# 13A-777.net
KiCad netlist of a schematic drawn in EAGLE
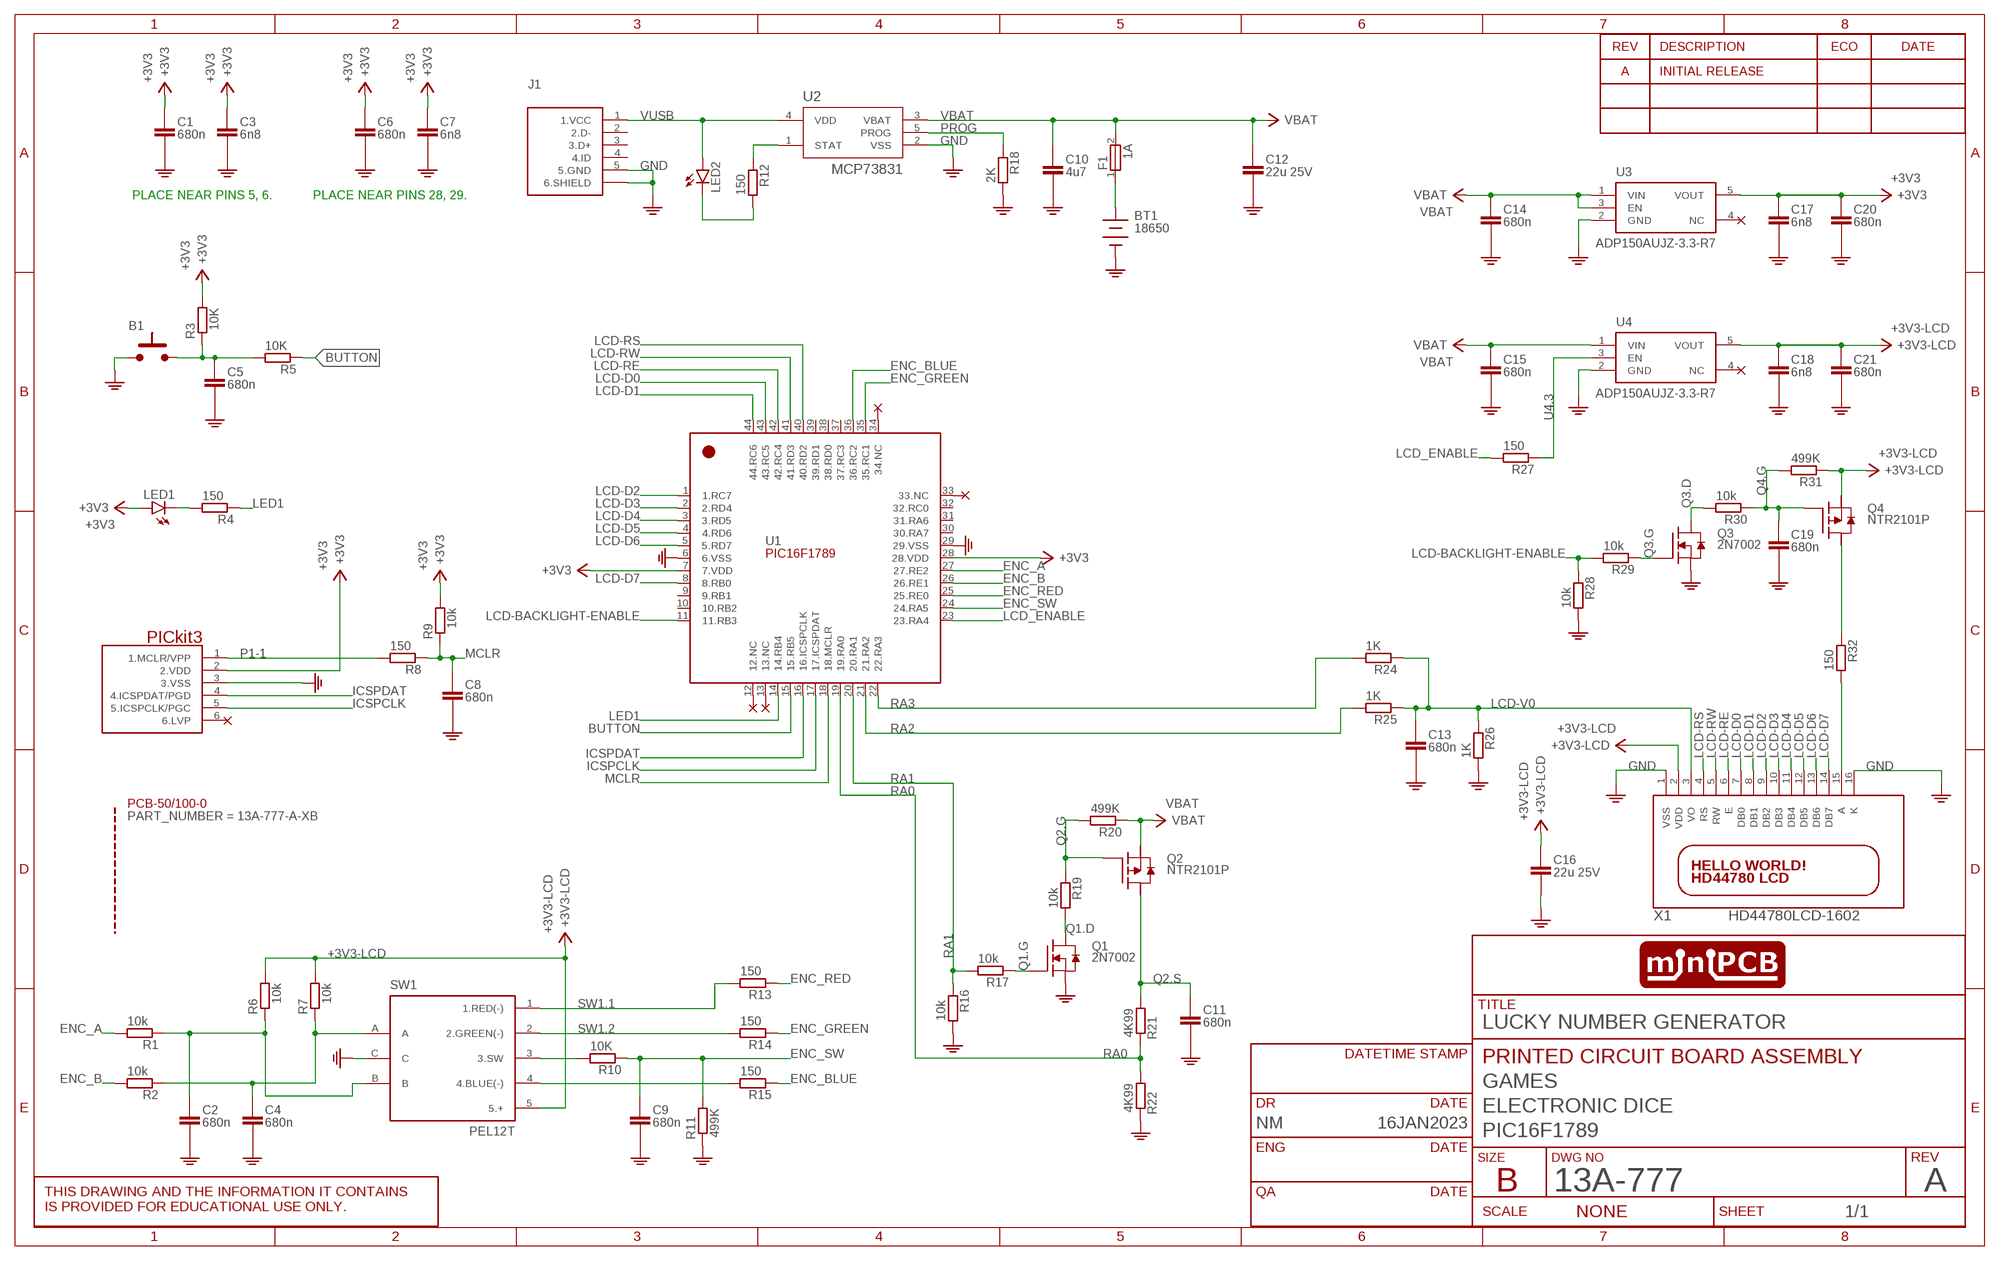
[diagram p0: schematic, sheet 1]

(export (version "E")
  (design (tool "Eeschema 10.0.6"))
  (components
    (comp (ref "B1")
      (value "PUSHBUTTON6X6MM")
      (footprint "eagle-import:6X6MM")
      (libsource (lib "eagle-import") (part "PUSHBUTTON6X6MM"))
    )
    (comp (ref "BT1")
      (value "18650")
      (footprint "eagle-import:BATTERY-18650-1-NOHOLES")
      (libsource (lib "eagle-import") (part "BATTERY18650-NOHOLES"))
    )
    (comp (ref "C1")
      (value "680n")
      (footprint "eagle-import:C1206")
      (libsource (lib "eagle-import") (part "CAPACITOR1206"))
    )
    (comp (ref "C2")
      (value "680n")
      (footprint "eagle-import:C1206")
      (libsource (lib "eagle-import") (part "CAPACITOR1206"))
    )
    (comp (ref "C3")
      (value "6n8")
      (footprint "eagle-import:C1206")
      (libsource (lib "eagle-import") (part "CAPACITOR1206"))
    )
    (comp (ref "C4")
      (value "680n")
      (footprint "eagle-import:C1206")
      (libsource (lib "eagle-import") (part "CAPACITOR1206"))
    )
    (comp (ref "C5")
      (value "680n")
      (footprint "eagle-import:C1206")
      (libsource (lib "eagle-import") (part "CAPACITOR1206"))
    )
    (comp (ref "C6")
      (value "680n")
      (footprint "eagle-import:C1206")
      (libsource (lib "eagle-import") (part "CAPACITOR1206"))
    )
    (comp (ref "C7")
      (value "6n8")
      (footprint "eagle-import:C1206")
      (libsource (lib "eagle-import") (part "CAPACITOR1206"))
    )
    (comp (ref "C8")
      (value "680n")
      (footprint "eagle-import:C1206")
      (libsource (lib "eagle-import") (part "CAPACITOR1206"))
    )
    (comp (ref "C9")
      (value "680n")
      (footprint "eagle-import:C1206")
      (libsource (lib "eagle-import") (part "CAPACITOR1206"))
    )
    (comp (ref "C10")
      (value "4u7")
      (footprint "eagle-import:C1206")
      (libsource (lib "eagle-import") (part "CAPACITOR1206"))
    )
    (comp (ref "C11")
      (value "680n")
      (footprint "eagle-import:C1206")
      (libsource (lib "eagle-import") (part "CAPACITOR1206"))
    )
    (comp (ref "C12")
      (value "22u 25V")
      (footprint "eagle-import:C3-5MM")
      (libsource (lib "eagle-import") (part "CAPACITOR3.5MM"))
    )
    (comp (ref "C13")
      (value "680n")
      (footprint "eagle-import:C1206")
      (libsource (lib "eagle-import") (part "CAPACITOR1206"))
    )
    (comp (ref "C14")
      (value "680n")
      (footprint "eagle-import:C1206")
      (libsource (lib "eagle-import") (part "CAPACITOR1206"))
    )
    (comp (ref "C15")
      (value "680n")
      (footprint "eagle-import:C1206")
      (libsource (lib "eagle-import") (part "CAPACITOR1206"))
    )
    (comp (ref "C16")
      (value "22u 25V")
      (footprint "eagle-import:C3-5MM")
      (libsource (lib "eagle-import") (part "CAPACITOR3.5MM"))
    )
    (comp (ref "C17")
      (value "6n8")
      (footprint "eagle-import:C1206")
      (libsource (lib "eagle-import") (part "CAPACITOR1206"))
    )
    (comp (ref "C18")
      (value "6n8")
      (footprint "eagle-import:C1206")
      (libsource (lib "eagle-import") (part "CAPACITOR1206"))
    )
    (comp (ref "C19")
      (value "680n")
      (footprint "eagle-import:C1206")
      (libsource (lib "eagle-import") (part "CAPACITOR1206"))
    )
    (comp (ref "C20")
      (value "680n")
      (footprint "eagle-import:C1206")
      (libsource (lib "eagle-import") (part "CAPACITOR1206"))
    )
    (comp (ref "C21")
      (value "680n")
      (footprint "eagle-import:C1206")
      (libsource (lib "eagle-import") (part "CAPACITOR1206"))
    )
    (comp (ref "F1")
      (value "1A")
      (footprint "eagle-import:1812L010DR")
      (fields
        (field (name "ARROW_PART_NUMBER") "1812L050/60MR")
        (field (name "MOUSER_PART_NUMBER") "576-1812L050/60MR")
      )
      (libsource (lib "eagle-import") (part "FUSE-1812-1A"))
    )
    (comp (ref "J1")
      (value "USB2LUG")
      (footprint "eagle-import:USB_MICRO_B")
      (libsource (lib "eagle-import") (part "USB2LUG"))
    )
    (comp (ref "LED1")
      (value "LEDCHIP-LED0805")
      (footprint "eagle-import:CHIP-LED0805")
      (libsource (lib "eagle-import") (part "LEDCHIP-LED0805"))
    )
    (comp (ref "LED2")
      (value "LEDCHIP-LED0805")
      (footprint "eagle-import:CHIP-LED0805")
      (libsource (lib "eagle-import") (part "LEDCHIP-LED0805"))
    )
    (comp (ref "PCB")
      (value "PCB-50/100-0")
      (footprint "eagle-import:MINIPCB_0P_50X100MM")
      (fields (field (name "PART_NUMBER") "13A-777-A-XB"))
      (libsource (lib "eagle-import") (part "MINIPCB_0P50X100MM"))
    )
    (comp (ref "Q1")
      (value "2N7002")
      (footprint "eagle-import:SOT23")
      (libsource (lib "eagle-import") (part "MOSFET-NSOT23"))
    )
    (comp (ref "Q2")
      (value "NTR2101P")
      (footprint "eagle-import:SOT23")
      (libsource (lib "eagle-import") (part "MOSFET-PNTR2101PT1G"))
    )
    (comp (ref "Q3")
      (value "2N7002")
      (footprint "eagle-import:SOT23")
      (libsource (lib "eagle-import") (part "MOSFET-NSOT23"))
    )
    (comp (ref "Q4")
      (value "NTR2101P")
      (footprint "eagle-import:SOT23")
      (libsource (lib "eagle-import") (part "MOSFET-PNTR2101PT1G"))
    )
    (comp (ref "R1")
      (value "10k")
      (footprint "eagle-import:R0805")
      (libsource (lib "eagle-import") (part "RESISTORSMD"))
    )
    (comp (ref "R2")
      (value "10k")
      (footprint "eagle-import:R0805")
      (libsource (lib "eagle-import") (part "RESISTORSMD"))
    )
    (comp (ref "R3")
      (value "10K")
      (footprint "eagle-import:R0805")
      (libsource (lib "eagle-import") (part "RESISTORSMD"))
    )
    (comp (ref "R4")
      (value "150")
      (footprint "eagle-import:R0805")
      (libsource (lib "eagle-import") (part "RESISTORSMD"))
    )
    (comp (ref "R5")
      (value "10K")
      (footprint "eagle-import:R0805")
      (libsource (lib "eagle-import") (part "RESISTORSMD"))
    )
    (comp (ref "R6")
      (value "10k")
      (footprint "eagle-import:R0805")
      (libsource (lib "eagle-import") (part "RESISTORSMD"))
    )
    (comp (ref "R7")
      (value "10k")
      (footprint "eagle-import:R0805")
      (libsource (lib "eagle-import") (part "RESISTORSMD"))
    )
    (comp (ref "R8")
      (value "150")
      (footprint "eagle-import:R0805")
      (libsource (lib "eagle-import") (part "RESISTORSMD"))
    )
    (comp (ref "R9")
      (value "10k")
      (footprint "eagle-import:R0805")
      (libsource (lib "eagle-import") (part "RESISTORSMD"))
    )
    (comp (ref "R10")
      (value "10K")
      (footprint "eagle-import:R0805")
      (libsource (lib "eagle-import") (part "RESISTORSMD"))
    )
    (comp (ref "R11")
      (value "499K")
      (footprint "eagle-import:R0805")
      (libsource (lib "eagle-import") (part "RESISTORSMD"))
    )
    (comp (ref "R12")
      (value "150")
      (footprint "eagle-import:R0805")
      (libsource (lib "eagle-import") (part "RESISTORSMD"))
    )
    (comp (ref "R13")
      (value "150")
      (footprint "eagle-import:R0805")
      (libsource (lib "eagle-import") (part "RESISTORSMD"))
    )
    (comp (ref "R14")
      (value "150")
      (footprint "eagle-import:R0805")
      (libsource (lib "eagle-import") (part "RESISTORSMD"))
    )
    (comp (ref "R15")
      (value "150")
      (footprint "eagle-import:R0805")
      (libsource (lib "eagle-import") (part "RESISTORSMD"))
    )
    (comp (ref "R16")
      (value "10k")
      (footprint "eagle-import:R0805")
      (libsource (lib "eagle-import") (part "RESISTORSMD"))
    )
    (comp (ref "R17")
      (value "10k")
      (footprint "eagle-import:R0805")
      (libsource (lib "eagle-import") (part "RESISTORSMD"))
    )
    (comp (ref "R18")
      (value "2K")
      (footprint "eagle-import:R0805")
      (libsource (lib "eagle-import") (part "RESISTORSMD"))
    )
    (comp (ref "R19")
      (value "10k")
      (footprint "eagle-import:R0805")
      (libsource (lib "eagle-import") (part "RESISTORSMD"))
    )
    (comp (ref "R20")
      (value "499K")
      (footprint "eagle-import:R0805")
      (libsource (lib "eagle-import") (part "RESISTORSMD"))
    )
    (comp (ref "R21")
      (value "4K99")
      (footprint "eagle-import:R0805")
      (libsource (lib "eagle-import") (part "RESISTORSMD"))
    )
    (comp (ref "R22")
      (value "4K99")
      (footprint "eagle-import:R0805")
      (libsource (lib "eagle-import") (part "RESISTORSMD"))
    )
    (comp (ref "R24")
      (value "1K")
      (footprint "eagle-import:R0805")
      (libsource (lib "eagle-import") (part "RESISTORSMD"))
    )
    (comp (ref "R25")
      (value "1K")
      (footprint "eagle-import:R0805")
      (libsource (lib "eagle-import") (part "RESISTORSMD"))
    )
    (comp (ref "R26")
      (value "1K")
      (footprint "eagle-import:R0805")
      (libsource (lib "eagle-import") (part "RESISTORSMD"))
    )
    (comp (ref "R27")
      (value "150")
      (footprint "eagle-import:R0805")
      (libsource (lib "eagle-import") (part "RESISTORSMD"))
    )
    (comp (ref "R28")
      (value "10k")
      (footprint "eagle-import:R0805")
      (libsource (lib "eagle-import") (part "RESISTORSMD"))
    )
    (comp (ref "R29")
      (value "10k")
      (footprint "eagle-import:R0805")
      (libsource (lib "eagle-import") (part "RESISTORSMD"))
    )
    (comp (ref "R30")
      (value "10k")
      (footprint "eagle-import:R0805")
      (libsource (lib "eagle-import") (part "RESISTORSMD"))
    )
    (comp (ref "R31")
      (value "499K")
      (footprint "eagle-import:R0805")
      (libsource (lib "eagle-import") (part "RESISTORSMD"))
    )
    (comp (ref "R32")
      (value "150")
      (footprint "eagle-import:R0805")
      (libsource (lib "eagle-import") (part "RESISTORSMD"))
    )
    (comp (ref "SW1")
      (value "PEL12T")
      (footprint "eagle-import:SWITCH-ROTARY_ENCODER-12MM")
      (libsource (lib "eagle-import") (part "SWITCH-ROTARY_ENCODER+SW+3LEDSPEL12T"))
    )
    (comp (ref "U$1")
      (value "PICKIT3ARROW")
      (footprint "eagle-import:PINS_6_PICKIT3")
      (libsource (lib "eagle-import") (part "PICKIT3ARROW"))
    )
    (comp (ref "U1")
      (value "PIC16F1789T-I/PT")
      (footprint "eagle-import:SQFP-S-10X10-44")
      (libsource (lib "eagle-import") (part "PIC16F1789"))
    )
    (comp (ref "U2")
      (value "MCP73831")
      (footprint "eagle-import:SOT-23-5_MC_MCH")
      (fields
        (field (name "MANUFACTURER_PART_NUMBER") "MCP73831T-2ATI/OT")
        (field (name "COPYRIGHT") "Copyright (C) 2023 Ultra Librarian. All rights reserved.")
      )
      (libsource (lib "eagle-import") (part "MCP73831T-2ATI/OTSOT-23-5_MC_MCH"))
    )
    (comp (ref "U3")
      (value "ADP150AUJZ-3.3-R7")
      (footprint "eagle-import:SOT25")
      (libsource (lib "eagle-import") (part "ADP150"))
    )
    (comp (ref "U4")
      (value "ADP150AUJZ-3.3-R7")
      (footprint "eagle-import:SOT25")
      (libsource (lib "eagle-import") (part "ADP150"))
    )
    (comp (ref "X1")
      (value "HD44780LCD-1602")
      (footprint "eagle-import:LCD1602")
      (libsource (lib "eagle-import") (part "HD44780LCD-1602"))
    )
  )
  (nets
    (net (code "1") (name "+3V3") (class "Default")
      (node (ref "C1") (pin "+") (pinfunction "+_+") (pintype "passive"))
      (node (ref "C17") (pin "+") (pinfunction "+_+") (pintype "passive"))
      (node (ref "C20") (pin "+") (pinfunction "+_+") (pintype "passive"))
      (node (ref "C3") (pin "+") (pinfunction "+_+") (pintype "passive"))
      (node (ref "C6") (pin "+") (pinfunction "+_+") (pintype "passive"))
      (node (ref "C7") (pin "+") (pinfunction "+_+") (pintype "passive"))
      (node (ref "LED1") (pin "A") (pinfunction "A_A") (pintype "passive"))
      (node (ref "R3") (pin "2") (pinfunction "2_2") (pintype "passive"))
      (node (ref "R9") (pin "2") (pinfunction "2_2") (pintype "passive"))
      (node (ref "U$1") (pin "2") (pinfunction "2.VDD_2") (pintype "bidirectional"))
      (node (ref "U1") (pin "28") (pinfunction "28.VDD_28") (pintype "bidirectional"))
      (node (ref "U1") (pin "7") (pinfunction "7.VDD_7") (pintype "bidirectional"))
      (node (ref "U3") (pin "5") (pinfunction "VOUT_5") (pintype "bidirectional"))
    )
    (net (code "2") (name "+3V3-LCD") (class "Default")
      (node (ref "C16") (pin "+") (pinfunction "+_+") (pintype "passive"))
      (node (ref "C18") (pin "+") (pinfunction "+_+") (pintype "passive"))
      (node (ref "C21") (pin "+") (pinfunction "+_+") (pintype "passive"))
      (node (ref "Q4") (pin "3") (pinfunction "S_3") (pintype "passive"))
      (node (ref "R31") (pin "1") (pinfunction "1_1") (pintype "passive"))
      (node (ref "R6") (pin "2") (pinfunction "2_2") (pintype "passive"))
      (node (ref "R7") (pin "2") (pinfunction "2_2") (pintype "passive"))
      (node (ref "SW1") (pin "5") (pinfunction "5.+_5") (pintype "bidirectional"))
      (node (ref "U4") (pin "5") (pinfunction "VOUT_5") (pintype "bidirectional"))
      (node (ref "X1") (pin "2") (pinfunction "VDD_2") (pintype "power_in"))
    )
    (net (code "3") (name "/ENC_A") (class "Default")
      (node (ref "R1") (pin "2") (pinfunction "2_2") (pintype "passive"))
      (node (ref "U1") (pin "27") (pinfunction "27.RE2_27") (pintype "bidirectional"))
    )
    (net (code "4") (name "/ENC_B") (class "Default")
      (node (ref "R2") (pin "2") (pinfunction "2_2") (pintype "passive"))
      (node (ref "U1") (pin "26") (pinfunction "26.RE1_26") (pintype "bidirectional"))
    )
    (net (code "5") (name "/ENC_BLUE") (class "Default")
      (node (ref "R15") (pin "1") (pinfunction "1_1") (pintype "passive"))
      (node (ref "U1") (pin "36") (pinfunction "36.RC2_36") (pintype "bidirectional"))
    )
    (net (code "6") (name "/ENC_GREEN") (class "Default")
      (node (ref "R14") (pin "1") (pinfunction "1_1") (pintype "passive"))
      (node (ref "U1") (pin "35") (pinfunction "35.RC1_35") (pintype "bidirectional"))
    )
    (net (code "7") (name "/ENC_RED") (class "Default")
      (node (ref "R13") (pin "1") (pinfunction "1_1") (pintype "passive"))
      (node (ref "U1") (pin "25") (pinfunction "25.RE0_25") (pintype "bidirectional"))
    )
    (net (code "8") (name "/ENC_SW") (class "Default")
      (node (ref "C9") (pin "+") (pinfunction "+_+") (pintype "passive"))
      (node (ref "R10") (pin "1") (pinfunction "1_1") (pintype "passive"))
      (node (ref "R11") (pin "2") (pinfunction "2_2") (pintype "passive"))
      (node (ref "U1") (pin "24") (pinfunction "24.RA5_24") (pintype "bidirectional"))
    )
    (net (code "9") (name "/ICSPCLK") (class "Default")
      (node (ref "U$1") (pin "5") (pinfunction "5.ICSPCLK/PGC_5") (pintype "bidirectional"))
      (node (ref "U1") (pin "17") (pinfunction "17.ICSPDAT_17") (pintype "bidirectional"))
    )
    (net (code "10") (name "/ICSPDAT") (class "Default")
      (node (ref "U$1") (pin "4") (pinfunction "4.ICSPDAT/PGD_4") (pintype "bidirectional"))
      (node (ref "U1") (pin "16") (pinfunction "16.ICSPCLK_16") (pintype "bidirectional"))
    )
    (net (code "11") (name "/LCD-BACKLIGHT-ENABLE") (class "Default")
      (node (ref "R28") (pin "1") (pinfunction "1_1") (pintype "passive"))
      (node (ref "R29") (pin "2") (pinfunction "2_2") (pintype "passive"))
      (node (ref "U1") (pin "11") (pinfunction "11.RB3_11") (pintype "bidirectional"))
    )
    (net (code "12") (name "/LCD-D0") (class "Default")
      (node (ref "U1") (pin "43") (pinfunction "43.RC5_43") (pintype "bidirectional"))
      (node (ref "X1") (pin "7") (pinfunction "DB0_7") (pintype "bidirectional"))
    )
    (net (code "13") (name "/LCD-D1") (class "Default")
      (node (ref "U1") (pin "44") (pinfunction "44.RC6_44") (pintype "bidirectional"))
      (node (ref "X1") (pin "8") (pinfunction "DB1_8") (pintype "bidirectional"))
    )
    (net (code "14") (name "/LCD-D2") (class "Default")
      (node (ref "U1") (pin "1") (pinfunction "1.RC7_1") (pintype "bidirectional"))
      (node (ref "X1") (pin "9") (pinfunction "DB2_9") (pintype "bidirectional"))
    )
    (net (code "15") (name "/LCD-D3") (class "Default")
      (node (ref "U1") (pin "2") (pinfunction "2.RD4_2") (pintype "bidirectional"))
      (node (ref "X1") (pin "10") (pinfunction "DB3_10") (pintype "bidirectional"))
    )
    (net (code "16") (name "/LCD-D4") (class "Default")
      (node (ref "U1") (pin "3") (pinfunction "3.RD5_3") (pintype "bidirectional"))
      (node (ref "X1") (pin "11") (pinfunction "DB4_11") (pintype "bidirectional"))
    )
    (net (code "17") (name "/LCD-D5") (class "Default")
      (node (ref "U1") (pin "4") (pinfunction "4.RD6_4") (pintype "bidirectional"))
      (node (ref "X1") (pin "12") (pinfunction "DB5_12") (pintype "bidirectional"))
    )
    (net (code "18") (name "/LCD-D6") (class "Default")
      (node (ref "U1") (pin "5") (pinfunction "5.RD7_5") (pintype "bidirectional"))
      (node (ref "X1") (pin "13") (pinfunction "DB6_13") (pintype "bidirectional"))
    )
    (net (code "19") (name "/LCD-D7") (class "Default")
      (node (ref "U1") (pin "8") (pinfunction "8.RB0_8") (pintype "bidirectional"))
      (node (ref "X1") (pin "14") (pinfunction "DB7_14") (pintype "bidirectional"))
    )
    (net (code "20") (name "/LCD-RE") (class "Default")
      (node (ref "U1") (pin "42") (pinfunction "42.RC4_42") (pintype "bidirectional"))
      (node (ref "X1") (pin "6") (pinfunction "E_6") (pintype "input"))
    )
    (net (code "21") (name "/LCD-RS") (class "Default")
      (node (ref "U1") (pin "40") (pinfunction "40.RD2_40") (pintype "bidirectional"))
      (node (ref "X1") (pin "4") (pinfunction "RS_4") (pintype "input"))
    )
    (net (code "22") (name "/LCD-RW") (class "Default")
      (node (ref "U1") (pin "41") (pinfunction "41.RD3_41") (pintype "bidirectional"))
      (node (ref "X1") (pin "5") (pinfunction "RW_5") (pintype "input"))
    )
    (net (code "23") (name "/LCD-V0") (class "Default")
      (node (ref "C13") (pin "+") (pinfunction "+_+") (pintype "passive"))
      (node (ref "R24") (pin "1") (pinfunction "1_1") (pintype "passive"))
      (node (ref "R25") (pin "1") (pinfunction "1_1") (pintype "passive"))
      (node (ref "R26") (pin "1") (pinfunction "1_1") (pintype "passive"))
      (node (ref "X1") (pin "3") (pinfunction "VO_3") (pintype "input"))
    )
    (net (code "24") (name "/LCD_ENABLE") (class "Default")
      (node (ref "R27") (pin "2") (pinfunction "2_2") (pintype "passive"))
      (node (ref "U1") (pin "23") (pinfunction "23.RA4_23") (pintype "bidirectional"))
    )
    (net (code "25") (name "/LED1") (class "Default")
      (node (ref "R4") (pin "1") (pinfunction "1_1") (pintype "passive"))
      (node (ref "U1") (pin "14") (pinfunction "14.RB4_14") (pintype "bidirectional"))
    )
    (net (code "26") (name "/MCLR") (class "Default")
      (node (ref "C8") (pin "+") (pinfunction "+_+") (pintype "passive"))
      (node (ref "R8") (pin "1") (pinfunction "1_1") (pintype "passive"))
      (node (ref "R9") (pin "1") (pinfunction "1_1") (pintype "passive"))
      (node (ref "U1") (pin "18") (pinfunction "18.MCLR_18") (pintype "bidirectional"))
    )
    (net (code "27") (name "/P1-1") (class "Default")
      (node (ref "R8") (pin "2") (pinfunction "2_2") (pintype "passive"))
      (node (ref "U$1") (pin "1") (pinfunction "1.MCLR/VPP_1") (pintype "bidirectional"))
    )
    (net (code "28") (name "/PROG") (class "Default")
      (node (ref "R18") (pin "1") (pinfunction "1_1") (pintype "passive"))
      (node (ref "U2") (pin "5") (pinfunction "PROG_5") (pintype "passive"))
    )
    (net (code "29") (name "/Q1.D") (class "Default")
      (node (ref "Q1") (pin "3") (pinfunction "D_3") (pintype "passive"))
      (node (ref "R19") (pin "2") (pinfunction "2_2") (pintype "passive"))
    )
    (net (code "30") (name "/Q1.G") (class "Default")
      (node (ref "Q1") (pin "1") (pinfunction "G_1") (pintype "passive"))
      (node (ref "R17") (pin "1") (pinfunction "1_1") (pintype "passive"))
    )
    (net (code "31") (name "/Q2.G") (class "Default")
      (node (ref "Q2") (pin "1") (pinfunction "G_1") (pintype "passive"))
      (node (ref "R19") (pin "1") (pinfunction "1_1") (pintype "passive"))
      (node (ref "R20") (pin "2") (pinfunction "2_2") (pintype "passive"))
    )
    (net (code "32") (name "/Q2.S") (class "Default")
      (node (ref "C11") (pin "+") (pinfunction "+_+") (pintype "passive"))
      (node (ref "Q2") (pin "2") (pinfunction "D_2") (pintype "passive"))
      (node (ref "R21") (pin "2") (pinfunction "2_2") (pintype "passive"))
    )
    (net (code "33") (name "/Q3.D") (class "Default")
      (node (ref "Q3") (pin "3") (pinfunction "D_3") (pintype "passive"))
      (node (ref "R30") (pin "2") (pinfunction "2_2") (pintype "passive"))
    )
    (net (code "34") (name "/Q3.G") (class "Default")
      (node (ref "Q3") (pin "1") (pinfunction "G_1") (pintype "passive"))
      (node (ref "R29") (pin "1") (pinfunction "1_1") (pintype "passive"))
    )
    (net (code "35") (name "/Q4.G") (class "Default")
      (node (ref "C19") (pin "+") (pinfunction "+_+") (pintype "passive"))
      (node (ref "Q4") (pin "1") (pinfunction "G_1") (pintype "passive"))
      (node (ref "R30") (pin "1") (pinfunction "1_1") (pintype "passive"))
      (node (ref "R31") (pin "2") (pinfunction "2_2") (pintype "passive"))
    )
    (net (code "36") (name "/RA0") (class "Default")
      (node (ref "R21") (pin "1") (pinfunction "1_1") (pintype "passive"))
      (node (ref "R22") (pin "2") (pinfunction "2_2") (pintype "passive"))
      (node (ref "U1") (pin "19") (pinfunction "19.RA0_19") (pintype "bidirectional"))
    )
    (net (code "37") (name "/RA1") (class "Default")
      (node (ref "R16") (pin "1") (pinfunction "1_1") (pintype "passive"))
      (node (ref "R17") (pin "2") (pinfunction "2_2") (pintype "passive"))
      (node (ref "U1") (pin "20") (pinfunction "20.RA1_20") (pintype "bidirectional"))
    )
    (net (code "38") (name "/RA2") (class "Default")
      (node (ref "R25") (pin "2") (pinfunction "2_2") (pintype "passive"))
      (node (ref "U1") (pin "21") (pinfunction "21.RA2_21") (pintype "bidirectional"))
    )
    (net (code "39") (name "/RA3") (class "Default")
      (node (ref "R24") (pin "2") (pinfunction "2_2") (pintype "passive"))
      (node (ref "U1") (pin "22") (pinfunction "22.RA3_22") (pintype "bidirectional"))
    )
    (net (code "40") (name "/SW1.1") (class "Default")
      (node (ref "R13") (pin "2") (pinfunction "2_2") (pintype "passive"))
      (node (ref "SW1") (pin "1") (pinfunction "1.RED(-)_1") (pintype "bidirectional"))
    )
    (net (code "41") (name "/SW1.2") (class "Default")
      (node (ref "R14") (pin "2") (pinfunction "2_2") (pintype "passive"))
      (node (ref "SW1") (pin "2") (pinfunction "2.GREEN(-)_2") (pintype "bidirectional"))
    )
    (net (code "42") (name "/U4.3") (class "Default")
      (node (ref "R27") (pin "1") (pinfunction "1_1") (pintype "passive"))
      (node (ref "U4") (pin "3") (pinfunction "EN_3") (pintype "bidirectional"))
    )
    (net (code "43") (name "/VUSB") (class "Default")
      (node (ref "J1") (pin "1") (pinfunction "1.VCC_1") (pintype "bidirectional"))
      (node (ref "LED2") (pin "A") (pinfunction "A_A") (pintype "passive"))
      (node (ref "U2") (pin "4") (pinfunction "VDD_4") (pintype "passive"))
    )
    (net (code "44") (name "BUTTON") (class "Default")
      (node (ref "R5") (pin "1") (pinfunction "1_1") (pintype "passive"))
      (node (ref "U1") (pin "15") (pinfunction "15.RB5_15") (pintype "bidirectional"))
    )
    (net (code "45") (name "GND") (class "Default")
      (node (ref "B1") (pin "1.A") (pinfunction "1_1.A") (pintype "bidirectional"))
      (node (ref "B1") (pin "2.A") (pinfunction "1_2.A") (pintype "bidirectional"))
      (node (ref "BT1") (pin "1") (pinfunction "-_1") (pintype "bidirectional"))
      (node (ref "C1") (pin "-") (pinfunction "-_-") (pintype "passive"))
      (node (ref "C10") (pin "-") (pinfunction "-_-") (pintype "passive"))
      (node (ref "C11") (pin "-") (pinfunction "-_-") (pintype "passive"))
      (node (ref "C12") (pin "-") (pinfunction "-_-") (pintype "passive"))
      (node (ref "C13") (pin "-") (pinfunction "-_-") (pintype "passive"))
      (node (ref "C14") (pin "-") (pinfunction "-_-") (pintype "passive"))
      (node (ref "C15") (pin "-") (pinfunction "-_-") (pintype "passive"))
      (node (ref "C16") (pin "-") (pinfunction "-_-") (pintype "passive"))
      (node (ref "C17") (pin "-") (pinfunction "-_-") (pintype "passive"))
      (node (ref "C18") (pin "-") (pinfunction "-_-") (pintype "passive"))
      (node (ref "C19") (pin "-") (pinfunction "-_-") (pintype "passive"))
      (node (ref "C2") (pin "-") (pinfunction "-_-") (pintype "passive"))
      (node (ref "C20") (pin "-") (pinfunction "-_-") (pintype "passive"))
      (node (ref "C21") (pin "-") (pinfunction "-_-") (pintype "passive"))
      (node (ref "C3") (pin "-") (pinfunction "-_-") (pintype "passive"))
      (node (ref "C4") (pin "-") (pinfunction "-_-") (pintype "passive"))
      (node (ref "C5") (pin "-") (pinfunction "-_-") (pintype "passive"))
      (node (ref "C6") (pin "-") (pinfunction "-_-") (pintype "passive"))
      (node (ref "C7") (pin "-") (pinfunction "-_-") (pintype "passive"))
      (node (ref "C8") (pin "-") (pinfunction "-_-") (pintype "passive"))
      (node (ref "C9") (pin "-") (pinfunction "-_-") (pintype "passive"))
      (node (ref "J1") (pin "5") (pinfunction "5.GND_5") (pintype "bidirectional"))
      (node (ref "J1") (pin "GND10") (pinfunction "6.SHIELD_GND10") (pintype "bidirectional"))
      (node (ref "J1") (pin "GND5") (pinfunction "6.SHIELD_GND5") (pintype "bidirectional"))
      (node (ref "J1") (pin "GND6") (pinfunction "6.SHIELD_GND6") (pintype "bidirectional"))
      (node (ref "J1") (pin "GND7") (pinfunction "6.SHIELD_GND7") (pintype "bidirectional"))
      (node (ref "J1") (pin "GND8") (pinfunction "6.SHIELD_GND8") (pintype "bidirectional"))
      (node (ref "J1") (pin "GND9") (pinfunction "6.SHIELD_GND9") (pintype "bidirectional"))
      (node (ref "J1") (pin "XPAD3") (pinfunction "6.SHIELD_XPAD3") (pintype "bidirectional"))
      (node (ref "J1") (pin "XPAD4") (pinfunction "6.SHIELD_XPAD4") (pintype "bidirectional"))
      (node (ref "Q1") (pin "2") (pinfunction "S_2") (pintype "passive"))
      (node (ref "Q3") (pin "2") (pinfunction "S_2") (pintype "passive"))
      (node (ref "R11") (pin "1") (pinfunction "1_1") (pintype "passive"))
      (node (ref "R16") (pin "2") (pinfunction "2_2") (pintype "passive"))
      (node (ref "R18") (pin "2") (pinfunction "2_2") (pintype "passive"))
      (node (ref "R22") (pin "1") (pinfunction "1_1") (pintype "passive"))
      (node (ref "R26") (pin "2") (pinfunction "2_2") (pintype "passive"))
      (node (ref "R28") (pin "2") (pinfunction "2_2") (pintype "passive"))
      (node (ref "SW1") (pin "C") (pinfunction "C_C") (pintype "bidirectional"))
      (node (ref "U$1") (pin "3") (pinfunction "3.VSS_3") (pintype "bidirectional"))
      (node (ref "U1") (pin "29") (pinfunction "29.VSS_29") (pintype "bidirectional"))
      (node (ref "U1") (pin "6") (pinfunction "6.VSS_6") (pintype "bidirectional"))
      (node (ref "U2") (pin "2") (pinfunction "VSS_2") (pintype "passive"))
      (node (ref "U3") (pin "2") (pinfunction "GND_2") (pintype "bidirectional"))
      (node (ref "U4") (pin "2") (pinfunction "GND_2") (pintype "bidirectional"))
      (node (ref "X1") (pin "1") (pinfunction "VSS_1") (pintype "power_in"))
      (node (ref "X1") (pin "16") (pinfunction "K_16") (pintype "input"))
    )
    (net (code "46") (name "Net-(B1-2-Pad3.B)") (class "Default")
      (node (ref "B1") (pin "3.B") (pinfunction "2_3.B") (pintype "bidirectional"))
      (node (ref "B1") (pin "4.B") (pinfunction "2_4.B") (pintype "bidirectional"))
      (node (ref "C5") (pin "+") (pinfunction "+_+") (pintype "passive"))
      (node (ref "R3") (pin "1") (pinfunction "1_1") (pintype "passive"))
      (node (ref "R5") (pin "2") (pinfunction "2_2") (pintype "passive"))
    )
    (net (code "47") (name "Net-(BT1-Pad+)") (class "Default")
      (node (ref "BT1") (pin "+") (pinfunction "+_+") (pintype "bidirectional"))
      (node (ref "F1") (pin "1") (pinfunction "1_1") (pintype "bidirectional"))
    )
    (net (code "48") (name "Net-(C2-Pad+)") (class "Default")
      (node (ref "C2") (pin "+") (pinfunction "+_+") (pintype "passive"))
      (node (ref "R1") (pin "1") (pinfunction "1_1") (pintype "passive"))
      (node (ref "R6") (pin "1") (pinfunction "1_1") (pintype "passive"))
      (node (ref "SW1") (pin "B") (pinfunction "B_B") (pintype "bidirectional"))
    )
    (net (code "49") (name "Net-(C4-Pad+)") (class "Default")
      (node (ref "C4") (pin "+") (pinfunction "+_+") (pintype "passive"))
      (node (ref "R2") (pin "1") (pinfunction "1_1") (pintype "passive"))
      (node (ref "R7") (pin "1") (pinfunction "1_1") (pintype "passive"))
      (node (ref "SW1") (pin "A") (pinfunction "A_A") (pintype "bidirectional"))
    )
    (net (code "50") (name "Net-(LED1-PadC)") (class "Default")
      (node (ref "LED1") (pin "C") (pinfunction "C_C") (pintype "passive"))
      (node (ref "R4") (pin "2") (pinfunction "2_2") (pintype "passive"))
    )
    (net (code "51") (name "Net-(LED2-PadC)") (class "Default")
      (node (ref "LED2") (pin "C") (pinfunction "C_C") (pintype "passive"))
      (node (ref "R12") (pin "2") (pinfunction "2_2") (pintype "passive"))
    )
    (net (code "52") (name "Net-(Q4-D)") (class "Default")
      (node (ref "Q4") (pin "2") (pinfunction "D_2") (pintype "passive"))
      (node (ref "R32") (pin "1") (pinfunction "1_1") (pintype "passive"))
    )
    (net (code "53") (name "Net-(SW1-3.SW)") (class "Default")
      (node (ref "R10") (pin "2") (pinfunction "2_2") (pintype "passive"))
      (node (ref "SW1") (pin "3") (pinfunction "3.SW_3") (pintype "bidirectional"))
    )
    (net (code "54") (name "Net-(SW1-4.BLUE(-))") (class "Default")
      (node (ref "R15") (pin "2") (pinfunction "2_2") (pintype "passive"))
      (node (ref "SW1") (pin "4") (pinfunction "4.BLUE(-)_4") (pintype "bidirectional"))
    )
    (net (code "55") (name "Net-(U2-STAT)") (class "Default")
      (node (ref "R12") (pin "1") (pinfunction "1_1") (pintype "passive"))
      (node (ref "U2") (pin "1") (pinfunction "STAT_1") (pintype "passive"))
    )
    (net (code "56") (name "Net-(X1-A)") (class "Default")
      (node (ref "R32") (pin "2") (pinfunction "2_2") (pintype "passive"))
      (node (ref "X1") (pin "15") (pinfunction "A_15") (pintype "input"))
    )
    (net (code "57") (name "VBAT") (class "Default")
      (node (ref "C10") (pin "+") (pinfunction "+_+") (pintype "passive"))
      (node (ref "C12") (pin "+") (pinfunction "+_+") (pintype "passive"))
      (node (ref "C14") (pin "+") (pinfunction "+_+") (pintype "passive"))
      (node (ref "C15") (pin "+") (pinfunction "+_+") (pintype "passive"))
      (node (ref "F1") (pin "2") (pinfunction "2_2") (pintype "bidirectional"))
      (node (ref "Q2") (pin "3") (pinfunction "S_3") (pintype "passive"))
      (node (ref "R20") (pin "1") (pinfunction "1_1") (pintype "passive"))
      (node (ref "U2") (pin "3") (pinfunction "VBAT_3") (pintype "passive"))
      (node (ref "U3") (pin "1") (pinfunction "VIN_1") (pintype "bidirectional"))
      (node (ref "U3") (pin "3") (pinfunction "EN_3") (pintype "bidirectional"))
      (node (ref "U4") (pin "1") (pinfunction "VIN_1") (pintype "bidirectional"))
    )
    (net (code "58") (name "unconnected-(J1-2.D--Pad2)") (class "Default")
      (node (ref "J1") (pin "2") (pinfunction "2.D-_2") (pintype "bidirectional"))
    )
    (net (code "59") (name "unconnected-(J1-3.D+-Pad3)") (class "Default")
      (node (ref "J1") (pin "3") (pinfunction "3.D+_3") (pintype "bidirectional"))
    )
    (net (code "60") (name "unconnected-(J1-4.ID-Pad4)") (class "Default")
      (node (ref "J1") (pin "4") (pinfunction "4.ID_4") (pintype "bidirectional"))
    )
    (net (code "61") (name "unconnected-(U$1-6.LVP-Pad6)") (class "Default")
      (node (ref "U$1") (pin "6") (pinfunction "6.LVP_6") (pintype "bidirectional"))
    )
    (net (code "62") (name "unconnected-(U1-9.RB1-Pad9)") (class "Default")
      (node (ref "U1") (pin "9") (pinfunction "9.RB1_9") (pintype "bidirectional"))
    )
    (net (code "63") (name "unconnected-(U1-10.RB2-Pad10)") (class "Default")
      (node (ref "U1") (pin "10") (pinfunction "10.RB2_10") (pintype "bidirectional"))
    )
    (net (code "64") (name "unconnected-(U1-12.NC-Pad12)") (class "Default")
      (node (ref "U1") (pin "12") (pinfunction "12.NC_12") (pintype "bidirectional"))
    )
    (net (code "65") (name "unconnected-(U1-13.NC-Pad13)") (class "Default")
      (node (ref "U1") (pin "13") (pinfunction "13.NC_13") (pintype "bidirectional"))
    )
    (net (code "66") (name "unconnected-(U1-30.RA7-Pad30)") (class "Default")
      (node (ref "U1") (pin "30") (pinfunction "30.RA7_30") (pintype "bidirectional"))
    )
    (net (code "67") (name "unconnected-(U1-31.RA6-Pad31)") (class "Default")
      (node (ref "U1") (pin "31") (pinfunction "31.RA6_31") (pintype "bidirectional"))
    )
    (net (code "68") (name "unconnected-(U1-32.RC0-Pad32)") (class "Default")
      (node (ref "U1") (pin "32") (pinfunction "32.RC0_32") (pintype "bidirectional"))
    )
    (net (code "69") (name "unconnected-(U1-33.NC-Pad33)") (class "Default")
      (node (ref "U1") (pin "33") (pinfunction "33.NC_33") (pintype "bidirectional"))
    )
    (net (code "70") (name "unconnected-(U1-34.NC-Pad34)") (class "Default")
      (node (ref "U1") (pin "34") (pinfunction "34.NC_34") (pintype "bidirectional"))
    )
    (net (code "71") (name "unconnected-(U1-37.RC3-Pad37)") (class "Default")
      (node (ref "U1") (pin "37") (pinfunction "37.RC3_37") (pintype "bidirectional"))
    )
    (net (code "72") (name "unconnected-(U1-38.RD0-Pad38)") (class "Default")
      (node (ref "U1") (pin "38") (pinfunction "38.RD0_38") (pintype "bidirectional"))
    )
    (net (code "73") (name "unconnected-(U1-39.RD1-Pad39)") (class "Default")
      (node (ref "U1") (pin "39") (pinfunction "39.RD1_39") (pintype "bidirectional"))
    )
    (net (code "74") (name "unconnected-(U3-NC-Pad4)") (class "Default")
      (node (ref "U3") (pin "4") (pinfunction "NC_4") (pintype "bidirectional"))
    )
    (net (code "75") (name "unconnected-(U4-NC-Pad4)") (class "Default")
      (node (ref "U4") (pin "4") (pinfunction "NC_4") (pintype "bidirectional"))
    )
  )
)
